# 00_DACs.net
KiCad netlist of a schematic drawn in Altium Designer
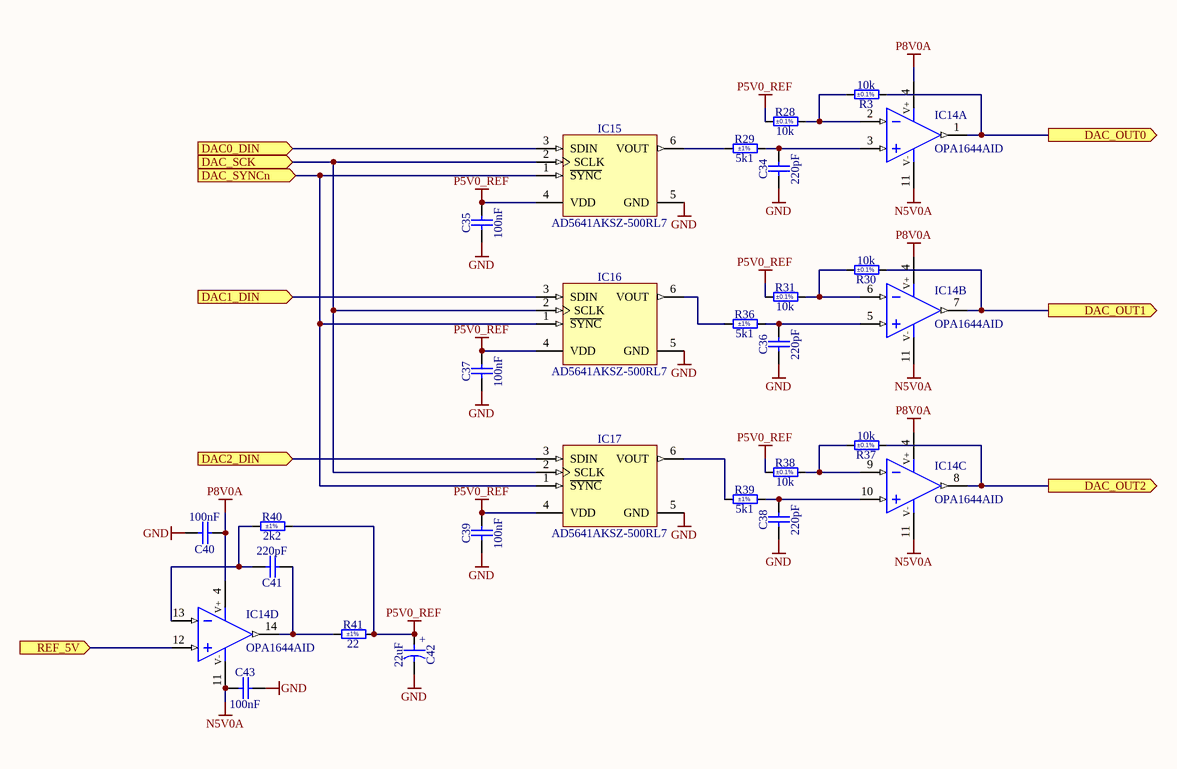
[diagram p0: [00] DACs.SchDoc]

(export (version "E")
  (design (tool "Eeschema 10.0.6"))
  (components
    (comp (ref "C34")
      (value "220pF")
      (footprint "CAPC1608X87N")
      (description "Non-polarised capacitor")
      (fields
        (field (name "PART NUMBER") "CC0603_220PF_50V_5%_NP0")
        (field (name "VOLTAGE") "50V")
        (field (name "AUTHOR") "CERN DEM JLC")
      )
      (libsource (lib "Capacitors") (part "Capacitor - non polarized"))
    )
    (comp (ref "C35")
      (value "100nF")
      (footprint "CAPC1005X55N")
      (description "Non-polarised capacitor")
      (fields
        (field (name "PART NUMBER") "CC0402_100NF_16V_10%_X7R")
        (field (name "VOLTAGE") "16V")
        (field (name "AUTHOR") "CERN DEM JLC")
      )
      (libsource (lib "Capacitors") (part "Capacitor - non polarized"))
    )
    (comp (ref "C36")
      (value "220pF")
      (footprint "CAPC1608X87N")
      (description "Non-polarised capacitor")
      (fields
        (field (name "PART NUMBER") "CC0603_220PF_50V_5%_NP0")
        (field (name "VOLTAGE") "50V")
        (field (name "AUTHOR") "CERN DEM JLC")
      )
      (libsource (lib "Capacitors") (part "Capacitor - non polarized"))
    )
    (comp (ref "C37")
      (value "100nF")
      (footprint "CAPC1005X55N")
      (description "Non-polarised capacitor")
      (fields
        (field (name "PART NUMBER") "CC0402_100NF_16V_10%_X7R")
        (field (name "VOLTAGE") "16V")
        (field (name "AUTHOR") "CERN DEM JLC")
      )
      (libsource (lib "Capacitors") (part "Capacitor - non polarized"))
    )
    (comp (ref "C38")
      (value "220pF")
      (footprint "CAPC1608X87N")
      (description "Non-polarised capacitor")
      (fields
        (field (name "PART NUMBER") "CC0603_220PF_50V_5%_NP0")
        (field (name "VOLTAGE") "50V")
        (field (name "AUTHOR") "CERN DEM JLC")
      )
      (libsource (lib "Capacitors") (part "Capacitor - non polarized"))
    )
    (comp (ref "C39")
      (value "100nF")
      (footprint "CAPC1005X55N")
      (description "Non-polarised capacitor")
      (fields
        (field (name "PART NUMBER") "CC0402_100NF_16V_10%_X7R")
        (field (name "VOLTAGE") "16V")
        (field (name "AUTHOR") "CERN DEM JLC")
      )
      (libsource (lib "Capacitors") (part "Capacitor - non polarized"))
    )
    (comp (ref "C40")
      (value "100nF")
      (footprint "CAPC1005X55N")
      (description "Non-polarised capacitor")
      (fields
        (field (name "PART NUMBER") "CC0402_100NF_16V_10%_X7R")
        (field (name "VOLTAGE") "16V")
        (field (name "AUTHOR") "CERN DEM JLC")
      )
      (libsource (lib "Capacitors") (part "Capacitor - non polarized"))
    )
    (comp (ref "C41")
      (value "220pF")
      (footprint "CAPC1608X87N")
      (description "Non-polarised capacitor")
      (fields
        (field (name "PART NUMBER") "CC0603_220PF_50V_5%_NP0")
        (field (name "VOLTAGE") "50V")
        (field (name "AUTHOR") "CERN DEM JLC")
      )
      (libsource (lib "Capacitors") (part "Capacitor - non polarized"))
    )
    (comp (ref "C42")
      (value "22uF")
      (footprint "CAPMP3528X210N")
      (description "Polarised capacitor")
      (fields
        (field (name "PART NUMBER") "CTE3528-21_22UF_20V_10%_LESR0400")
        (field (name "VOLTAGE") "20V")
        (field (name "AUTHOR") "CERN DEM JLC")
      )
      (libsource (lib "Capacitors") (part "Capacitor - polarized"))
    )
    (comp (ref "C43")
      (value "100nF")
      (footprint "CAPC1005X55N")
      (description "Non-polarised capacitor")
      (fields
        (field (name "PART NUMBER") "CC0402_100NF_16V_10%_X7R")
        (field (name "VOLTAGE") "16V")
        (field (name "AUTHOR") "CERN DEM JLC")
      )
      (libsource (lib "Capacitors") (part "Capacitor - non polarized"))
    )
    (comp (ref "IC14")
      (value "OPA1644AID")
      (footprint "SOIC127P600X175-14N")
      (description "Quad Operational Amplifier")
      (fields (field (name "MANUFACTURER") "TEXAS INSTRUMENTS") (field (name "AUTHOR") "CERN DEM JLC"))
      (libsource (lib "ICs And Semiconductors") (part "Operational Amplifier x4 Type1"))
    )
    (comp (ref "IC15")
      (value "AD5641AKSZ-500RL7")
      (footprint "SOT65P210X110-6N")
      (description "2.7V to 5.5V, <100µA, 14-Bit nanoDAC, SPI Interface")
      (fields
        (field (name "MANUFACTURER") "ANALOG DEVICES")
        (field (name "MANUFACTURER PART NUMBER") "AD5641AKS")
        (field (name "AUTHOR") "CERN DEM JLC")
      )
      (libsource (lib "ICs And Semiconductors") (part "AD5641"))
    )
    (comp (ref "IC16")
      (value "AD5641AKSZ-500RL7")
      (footprint "SOT65P210X110-6N")
      (description "2.7V to 5.5V, <100µA, 14-Bit nanoDAC, SPI Interface")
      (fields
        (field (name "MANUFACTURER") "ANALOG DEVICES")
        (field (name "MANUFACTURER PART NUMBER") "AD5641AKS")
        (field (name "AUTHOR") "CERN DEM JLC")
      )
      (libsource (lib "ICs And Semiconductors") (part "AD5641"))
    )
    (comp (ref "IC17")
      (value "AD5641AKSZ-500RL7")
      (footprint "SOT65P210X110-6N")
      (description "2.7V to 5.5V, <100µA, 14-Bit nanoDAC, SPI Interface")
      (fields
        (field (name "MANUFACTURER") "ANALOG DEVICES")
        (field (name "MANUFACTURER PART NUMBER") "AD5641AKS")
        (field (name "AUTHOR") "CERN DEM JLC")
      )
      (libsource (lib "ICs And Semiconductors") (part "AD5641"))
    )
    (comp (ref "R3")
      (value "10k")
      (footprint "RESC1608X64N")
      (description "Resistor - 0.1%")
      (fields
        (field (name "TOLERANCE") "±0.1%")
        (field (name "PART NUMBER") "R0603_10K_0.1%_0.1W_25PPM")
        (field (name "POWER") "0.1W")
        (field (name "AUTHOR") "CERN DEM JMW")
      )
      (libsource (lib "Resistors") (part "Resistor - 0.1%"))
    )
    (comp (ref "R28")
      (value "10k")
      (footprint "RESC1608X64N")
      (description "Resistor - 0.1%")
      (fields
        (field (name "TOLERANCE") "±0.1%")
        (field (name "PART NUMBER") "R0603_10K_0.1%_0.1W_25PPM")
        (field (name "POWER") "0.1W")
        (field (name "AUTHOR") "CERN DEM JMW")
      )
      (libsource (lib "Resistors") (part "Resistor - 0.1%"))
    )
    (comp (ref "R29")
      (value "5k1")
      (footprint "RESC1608X55N")
      (description "Resistor - 1%")
      (fields
        (field (name "TOLERANCE") "±1%")
        (field (name "PART NUMBER") "R0603_5K1_1%_0.1W_100PPM")
        (field (name "POWER") "0.1W")
        (field (name "AUTHOR") "CERN DEM JLC")
      )
      (libsource (lib "Resistors") (part "Resistor - 1%"))
    )
    (comp (ref "R30")
      (value "10k")
      (footprint "RESC1608X64N")
      (description "Resistor - 0.1%")
      (fields
        (field (name "TOLERANCE") "±0.1%")
        (field (name "PART NUMBER") "R0603_10K_0.1%_0.1W_25PPM")
        (field (name "POWER") "0.1W")
        (field (name "AUTHOR") "CERN DEM JMW")
      )
      (libsource (lib "Resistors") (part "Resistor - 0.1%"))
    )
    (comp (ref "R31")
      (value "10k")
      (footprint "RESC1608X64N")
      (description "Resistor - 0.1%")
      (fields
        (field (name "TOLERANCE") "±0.1%")
        (field (name "PART NUMBER") "R0603_10K_0.1%_0.1W_25PPM")
        (field (name "POWER") "0.1W")
        (field (name "AUTHOR") "CERN DEM JMW")
      )
      (libsource (lib "Resistors") (part "Resistor - 0.1%"))
    )
    (comp (ref "R36")
      (value "5k1")
      (footprint "RESC1608X55N")
      (description "Resistor - 1%")
      (fields
        (field (name "TOLERANCE") "±1%")
        (field (name "PART NUMBER") "R0603_5K1_1%_0.1W_100PPM")
        (field (name "POWER") "0.1W")
        (field (name "AUTHOR") "CERN DEM JLC")
      )
      (libsource (lib "Resistors") (part "Resistor - 1%"))
    )
    (comp (ref "R37")
      (value "10k")
      (footprint "RESC1608X64N")
      (description "Resistor - 0.1%")
      (fields
        (field (name "TOLERANCE") "±0.1%")
        (field (name "PART NUMBER") "R0603_10K_0.1%_0.1W_25PPM")
        (field (name "POWER") "0.1W")
        (field (name "AUTHOR") "CERN DEM JMW")
      )
      (libsource (lib "Resistors") (part "Resistor - 0.1%"))
    )
    (comp (ref "R38")
      (value "10k")
      (footprint "RESC1608X64N")
      (description "Resistor - 0.1%")
      (fields
        (field (name "TOLERANCE") "±0.1%")
        (field (name "PART NUMBER") "R0603_10K_0.1%_0.1W_25PPM")
        (field (name "POWER") "0.1W")
        (field (name "AUTHOR") "CERN DEM JMW")
      )
      (libsource (lib "Resistors") (part "Resistor - 0.1%"))
    )
    (comp (ref "R39")
      (value "5k1")
      (footprint "RESC1608X55N")
      (description "Resistor - 1%")
      (fields
        (field (name "TOLERANCE") "±1%")
        (field (name "PART NUMBER") "R0603_5K1_1%_0.1W_100PPM")
        (field (name "POWER") "0.1W")
        (field (name "AUTHOR") "CERN DEM JLC")
      )
      (libsource (lib "Resistors") (part "Resistor - 1%"))
    )
    (comp (ref "R40")
      (value "2k2")
      (footprint "RESC1608X55N")
      (description "Resistor - 1%")
      (fields
        (field (name "TOLERANCE") "±1%")
        (field (name "PART NUMBER") "R0603_2K2_1%_0.1W_100PPM")
        (field (name "POWER") "0.1W")
        (field (name "AUTHOR") "CERN DEM JLC")
      )
      (libsource (lib "Resistors") (part "Resistor - 1%"))
    )
    (comp (ref "R41")
      (value "22")
      (footprint "RESC1005X40N")
      (description "Resistor - 1%")
      (fields
        (field (name "TOLERANCE") "±1%")
        (field (name "PART NUMBER") "R0402_22R_1%_0.0625W_100PPM")
        (field (name "POWER") "0.0625W")
        (field (name "AUTHOR") "CERN DEM JLC")
      )
      (libsource (lib "Resistors") (part "Resistor - 1%"))
    )
  )
  (nets
    (net (code "1") (name "/DAC0_DIN") (class "Default")
      (node (ref "IC15") (pin "3") (pinfunction "SDIN_3") (pintype "input"))
    )
    (net (code "2") (name "/DAC1_DIN") (class "Default")
      (node (ref "IC16") (pin "3") (pinfunction "SDIN_3") (pintype "input"))
    )
    (net (code "3") (name "/DAC2_DIN") (class "Default")
      (node (ref "IC17") (pin "3") (pinfunction "SDIN_3") (pintype "input"))
    )
    (net (code "4") (name "/DAC_OUT0") (class "Default")
      (node (ref "IC14") (pin "1") (pinfunction "OUT_1") (pintype "output"))
      (node (ref "R3") (pin "1") (pinfunction "1_1") (pintype "passive"))
    )
    (net (code "5") (name "/DAC_OUT1") (class "Default")
      (node (ref "IC14") (pin "7") (pinfunction "OUT_7") (pintype "output"))
      (node (ref "R30") (pin "1") (pinfunction "1_1") (pintype "passive"))
    )
    (net (code "6") (name "/DAC_OUT2") (class "Default")
      (node (ref "IC14") (pin "8") (pinfunction "OUT_8") (pintype "output"))
      (node (ref "R37") (pin "1") (pinfunction "1_1") (pintype "passive"))
    )
    (net (code "7") (name "/DAC_SCK") (class "Default")
      (node (ref "IC15") (pin "2") (pinfunction "SCLK_2") (pintype "input"))
      (node (ref "IC16") (pin "2") (pinfunction "SCLK_2") (pintype "input"))
      (node (ref "IC17") (pin "2") (pinfunction "SCLK_2") (pintype "input"))
    )
    (net (code "8") (name "/DAC_SYNCn") (class "Default")
      (node (ref "IC15") (pin "1") (pinfunction "~{SYNC}_1") (pintype "input"))
      (node (ref "IC16") (pin "1") (pinfunction "~{SYNC}_1") (pintype "input"))
      (node (ref "IC17") (pin "1") (pinfunction "~{SYNC}_1") (pintype "input"))
    )
    (net (code "9") (name "/REF_5V") (class "Default")
      (node (ref "IC14") (pin "12") (pinfunction "IN+_12") (pintype "input"))
    )
    (net (code "10") (name "GND") (class "Default")
      (node (ref "C34") (pin "1") (pinfunction "1_1") (pintype "passive"))
      (node (ref "C35") (pin "1") (pinfunction "1_1") (pintype "passive"))
      (node (ref "C36") (pin "1") (pinfunction "1_1") (pintype "passive"))
      (node (ref "C37") (pin "1") (pinfunction "1_1") (pintype "passive"))
      (node (ref "C38") (pin "1") (pinfunction "1_1") (pintype "passive"))
      (node (ref "C39") (pin "1") (pinfunction "1_1") (pintype "passive"))
      (node (ref "C40") (pin "1") (pinfunction "1_1") (pintype "passive"))
      (node (ref "C42") (pin "2") (pinfunction "2_2") (pintype "passive"))
      (node (ref "C43") (pin "1") (pinfunction "1_1") (pintype "passive"))
      (node (ref "IC15") (pin "5") (pinfunction "GND_5") (pintype "power_in"))
      (node (ref "IC16") (pin "5") (pinfunction "GND_5") (pintype "power_in"))
      (node (ref "IC17") (pin "5") (pinfunction "GND_5") (pintype "power_in"))
    )
    (net (code "11") (name "N5V0A") (class "Default")
      (node (ref "C43") (pin "2") (pinfunction "2_2") (pintype "passive"))
      (node (ref "IC14") (pin "11") (pinfunction "V-_11") (pintype "power_in"))
    )
    (net (code "12") (name "Net-(IC14A-IN+)") (class "Default")
      (node (ref "C34") (pin "2") (pinfunction "2_2") (pintype "passive"))
      (node (ref "IC14") (pin "3") (pinfunction "IN+_3") (pintype "input"))
      (node (ref "R29") (pin "2") (pinfunction "2_2") (pintype "passive"))
    )
    (net (code "13") (name "Net-(IC14A-IN-)") (class "Default")
      (node (ref "IC14") (pin "2") (pinfunction "IN-_2") (pintype "input"))
      (node (ref "R28") (pin "2") (pinfunction "2_2") (pintype "passive"))
      (node (ref "R3") (pin "2") (pinfunction "2_2") (pintype "passive"))
    )
    (net (code "14") (name "Net-(IC14B-IN+)") (class "Default")
      (node (ref "C36") (pin "2") (pinfunction "2_2") (pintype "passive"))
      (node (ref "IC14") (pin "5") (pinfunction "IN+_5") (pintype "input"))
      (node (ref "R36") (pin "2") (pinfunction "2_2") (pintype "passive"))
    )
    (net (code "15") (name "Net-(IC14B-IN-)") (class "Default")
      (node (ref "IC14") (pin "6") (pinfunction "IN-_6") (pintype "input"))
      (node (ref "R30") (pin "2") (pinfunction "2_2") (pintype "passive"))
      (node (ref "R31") (pin "2") (pinfunction "2_2") (pintype "passive"))
    )
    (net (code "16") (name "Net-(IC14C-IN+)") (class "Default")
      (node (ref "C38") (pin "2") (pinfunction "2_2") (pintype "passive"))
      (node (ref "IC14") (pin "10") (pinfunction "IN+_10") (pintype "input"))
      (node (ref "R39") (pin "2") (pinfunction "2_2") (pintype "passive"))
    )
    (net (code "17") (name "Net-(IC14C-IN-)") (class "Default")
      (node (ref "IC14") (pin "9") (pinfunction "IN-_9") (pintype "input"))
      (node (ref "R37") (pin "2") (pinfunction "2_2") (pintype "passive"))
      (node (ref "R38") (pin "2") (pinfunction "2_2") (pintype "passive"))
    )
    (net (code "18") (name "Net-(IC14D-IN-)") (class "Default")
      (node (ref "C41") (pin "2") (pinfunction "2_2") (pintype "passive"))
      (node (ref "IC14") (pin "13") (pinfunction "IN-_13") (pintype "input"))
      (node (ref "R40") (pin "1") (pinfunction "1_1") (pintype "passive"))
    )
    (net (code "19") (name "Net-(IC14D-OUT)") (class "Default")
      (node (ref "C41") (pin "1") (pinfunction "1_1") (pintype "passive"))
      (node (ref "IC14") (pin "14") (pinfunction "OUT_14") (pintype "output"))
      (node (ref "R41") (pin "1") (pinfunction "1_1") (pintype "passive"))
    )
    (net (code "20") (name "Net-(IC15-VOUT)") (class "Default")
      (node (ref "IC15") (pin "6") (pinfunction "VOUT_6") (pintype "output"))
      (node (ref "R29") (pin "1") (pinfunction "1_1") (pintype "passive"))
    )
    (net (code "21") (name "Net-(IC16-VOUT)") (class "Default")
      (node (ref "IC16") (pin "6") (pinfunction "VOUT_6") (pintype "output"))
      (node (ref "R36") (pin "1") (pinfunction "1_1") (pintype "passive"))
    )
    (net (code "22") (name "Net-(IC17-VOUT)") (class "Default")
      (node (ref "IC17") (pin "6") (pinfunction "VOUT_6") (pintype "output"))
      (node (ref "R39") (pin "1") (pinfunction "1_1") (pintype "passive"))
    )
    (net (code "23") (name "P5V0_REF") (class "Default")
      (node (ref "C35") (pin "2") (pinfunction "2_2") (pintype "passive"))
      (node (ref "C37") (pin "2") (pinfunction "2_2") (pintype "passive"))
      (node (ref "C39") (pin "2") (pinfunction "2_2") (pintype "passive"))
      (node (ref "C42") (pin "1") (pinfunction "1_1") (pintype "passive"))
      (node (ref "IC15") (pin "4") (pinfunction "VDD_4") (pintype "power_in"))
      (node (ref "IC16") (pin "4") (pinfunction "VDD_4") (pintype "power_in"))
      (node (ref "IC17") (pin "4") (pinfunction "VDD_4") (pintype "power_in"))
      (node (ref "R28") (pin "1") (pinfunction "1_1") (pintype "passive"))
      (node (ref "R31") (pin "1") (pinfunction "1_1") (pintype "passive"))
      (node (ref "R38") (pin "1") (pinfunction "1_1") (pintype "passive"))
      (node (ref "R40") (pin "2") (pinfunction "2_2") (pintype "passive"))
      (node (ref "R41") (pin "2") (pinfunction "2_2") (pintype "passive"))
    )
    (net (code "24") (name "P8V0A") (class "Default")
      (node (ref "C40") (pin "2") (pinfunction "2_2") (pintype "passive"))
      (node (ref "IC14") (pin "4") (pinfunction "V+_4") (pintype "power_in"))
    )
  )
)
